# ThermoActuator.net
KiCad netlist of a schematic drawn in EAGLE
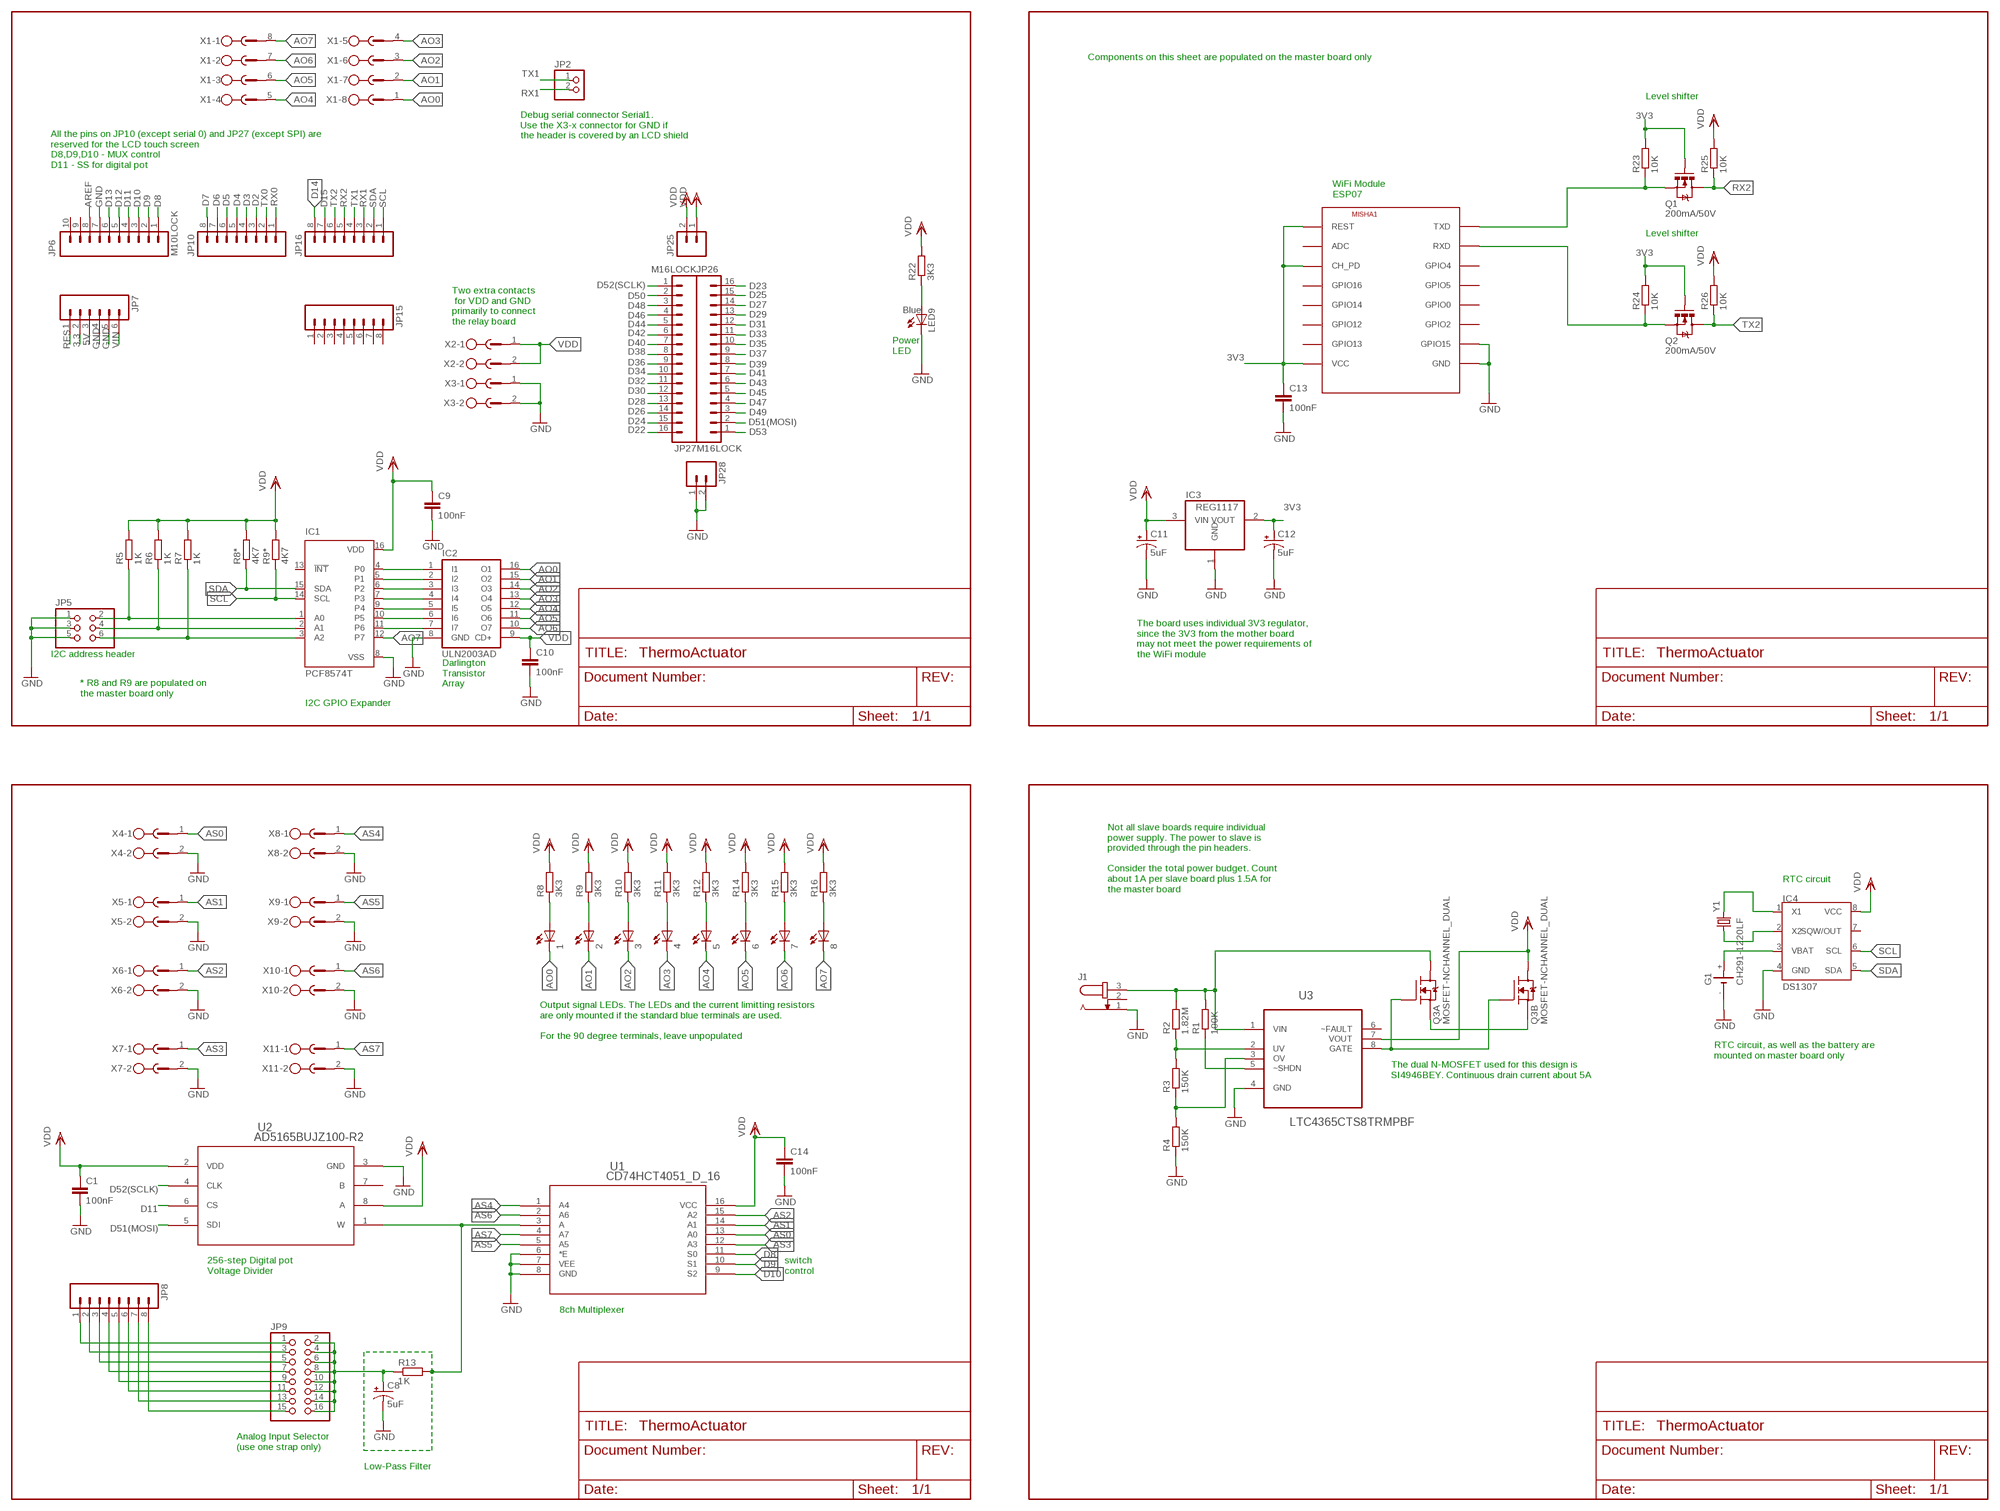
[diagram p0: schematic, sheet 1]

(export (version "E")
  (design (tool "Eeschema 10.0.6"))
  (components
    (comp (ref "1")
      (value "LEDCHIP-LED0805")
      (footprint "eagle-import:CHIP-LED0805")
      (libsource (lib "eagle-import") (part "LEDCHIP-LED0805"))
    )
    (comp (ref "2")
      (value "LEDCHIP-LED0805")
      (footprint "eagle-import:CHIP-LED0805")
      (libsource (lib "eagle-import") (part "LEDCHIP-LED0805"))
    )
    (comp (ref "3")
      (value "LEDCHIP-LED0805")
      (footprint "eagle-import:CHIP-LED0805")
      (libsource (lib "eagle-import") (part "LEDCHIP-LED0805"))
    )
    (comp (ref "4")
      (value "LEDCHIP-LED0805")
      (footprint "eagle-import:CHIP-LED0805")
      (libsource (lib "eagle-import") (part "LEDCHIP-LED0805"))
    )
    (comp (ref "5")
      (value "LEDCHIP-LED0805")
      (footprint "eagle-import:CHIP-LED0805")
      (libsource (lib "eagle-import") (part "LEDCHIP-LED0805"))
    )
    (comp (ref "6")
      (value "LEDCHIP-LED0805")
      (footprint "eagle-import:CHIP-LED0805")
      (libsource (lib "eagle-import") (part "LEDCHIP-LED0805"))
    )
    (comp (ref "7")
      (value "LEDCHIP-LED0805")
      (footprint "eagle-import:CHIP-LED0805")
      (libsource (lib "eagle-import") (part "LEDCHIP-LED0805"))
    )
    (comp (ref "8")
      (value "LEDCHIP-LED0805")
      (footprint "eagle-import:CHIP-LED0805")
      (libsource (lib "eagle-import") (part "LEDCHIP-LED0805"))
    )
    (comp (ref "C1")
      (value "100nF")
      (footprint "eagle-import:C0805")
      (libsource (lib "eagle-import") (part "C-EUC0805"))
    )
    (comp (ref "C8")
      (value "5uF")
      (footprint "eagle-import:EIA3216")
      (libsource (lib "eagle-import") (part "CAP_POL1206"))
    )
    (comp (ref "C9")
      (value "100nF")
      (footprint "eagle-import:C0805")
      (libsource (lib "eagle-import") (part "C-EUC0805"))
    )
    (comp (ref "C10")
      (value "100nF")
      (footprint "eagle-import:C0805")
      (libsource (lib "eagle-import") (part "C-EUC0805"))
    )
    (comp (ref "C11")
      (value "5uF")
      (footprint "eagle-import:EIA3216")
      (libsource (lib "eagle-import") (part "CAP_POL1206"))
    )
    (comp (ref "C12")
      (value "5uF")
      (footprint "eagle-import:EIA3216")
      (libsource (lib "eagle-import") (part "CAP_POL1206"))
    )
    (comp (ref "C13")
      (value "100nF")
      (footprint "eagle-import:C0805")
      (libsource (lib "eagle-import") (part "C-EUC0805"))
    )
    (comp (ref "C14")
      (value "100nF")
      (footprint "eagle-import:C0805")
      (libsource (lib "eagle-import") (part "C-EUC0805"))
    )
    (comp (ref "G1")
      (value "CH291-1220LF")
      (footprint "eagle-import:CH291-1220LF")
      (libsource (lib "eagle-import") (part "CH291-1220LF"))
    )
    (comp (ref "IC1")
      (value "PCF8574T")
      (footprint "eagle-import:SO16W")
      (fields (field (name "MPN") "PCF8574T/3,512"))
      (libsource (lib "eagle-import") (part "PCF8574T"))
    )
    (comp (ref "IC2")
      (value "ULN2003AD")
      (footprint "eagle-import:SO16")
      (libsource (lib "eagle-import") (part "ULN2003AD"))
    )
    (comp (ref "IC3")
      (value "REG1117")
      (footprint "eagle-import:SOT223")
      (libsource (lib "eagle-import") (part "REG1117"))
    )
    (comp (ref "IC4")
      (value "DS1307")
      (footprint "eagle-import:SOIC-8")
      (libsource (lib "eagle-import") (part "DS1307"))
    )
    (comp (ref "J1")
      (value "JACK-PLUG1")
      (footprint "eagle-import:SPC4078")
      (libsource (lib "eagle-import") (part "JACK-PLUG1"))
    )
    (comp (ref "JP2")
      (value "PINHD-1X2")
      (footprint "eagle-import:1X02")
      (libsource (lib "eagle-import") (part "PINHD-1X2"))
    )
    (comp (ref "JP5")
      (value "PINHD-2X3")
      (footprint "eagle-import:2X03")
      (libsource (lib "eagle-import") (part "PINHD-2X3"))
    )
    (comp (ref "JP6")
      (value "M10LOCK")
      (footprint "eagle-import:1X10_LOCK")
      (libsource (lib "eagle-import") (part "M10LOCK"))
    )
    (comp (ref "JP7")
      (value "M06LOCK")
      (footprint "eagle-import:1X06_LOCK")
      (libsource (lib "eagle-import") (part "M06LOCK"))
    )
    (comp (ref "JP8")
      (value "M08LOCK")
      (footprint "eagle-import:1X08_LOCK")
      (libsource (lib "eagle-import") (part "M08LOCK"))
    )
    (comp (ref "JP9")
      (value "PINHD-2X8")
      (footprint "eagle-import:2X08")
      (libsource (lib "eagle-import") (part "PINHD-2X8"))
    )
    (comp (ref "JP10")
      (value "M08LOCK")
      (footprint "eagle-import:1X08_LOCK")
      (libsource (lib "eagle-import") (part "M08LOCK"))
    )
    (comp (ref "JP15")
      (value "M08LOCK")
      (footprint "eagle-import:1X08_LOCK")
      (libsource (lib "eagle-import") (part "M08LOCK"))
    )
    (comp (ref "JP16")
      (value "M08LOCK")
      (footprint "eagle-import:1X08_LOCK")
      (libsource (lib "eagle-import") (part "M08LOCK"))
    )
    (comp (ref "JP25")
      (value "M02LOCK")
      (footprint "eagle-import:1X02_LOCK")
      (libsource (lib "eagle-import") (part "M02LOCK"))
    )
    (comp (ref "JP26")
      (value "M16LOCK")
      (footprint "eagle-import:1X16_LOCK")
      (libsource (lib "eagle-import") (part "M16LOCK"))
    )
    (comp (ref "JP27")
      (value "M16LOCK")
      (footprint "eagle-import:1X16_LOCK")
      (libsource (lib "eagle-import") (part "M16LOCK"))
    )
    (comp (ref "JP28")
      (value "M02LOCK")
      (footprint "eagle-import:1X02_LOCK")
      (libsource (lib "eagle-import") (part "M02LOCK"))
    )
    (comp (ref "LED9")
      (value "Blue")
      (footprint "eagle-import:CHIP-LED0805")
      (libsource (lib "eagle-import") (part "LEDCHIP-LED0805"))
    )
    (comp (ref "MISHA1")
      (value "ESP8266-07")
      (footprint "eagle-import:ESP-07")
      (libsource (lib "eagle-import") (part "ESP8266-07"))
    )
    (comp (ref "Q1")
      (value "200mA/50V")
      (footprint "eagle-import:SOT23-3")
      (libsource (lib "eagle-import") (part "MOSFET-NCHANNELBSS138"))
    )
    (comp (ref "Q2")
      (value "200mA/50V")
      (footprint "eagle-import:SOT23-3")
      (libsource (lib "eagle-import") (part "MOSFET-NCHANNELBSS138"))
    )
    (comp (ref "Q3")
      (value "MOSFET-NCHANNEL_DUAL")
      (footprint "eagle-import:SO08")
      (libsource (lib "eagle-import") (part "MOSFET-NCHANNEL_DUAL"))
    )
    (comp (ref "R1")
      (value "100K")
      (footprint "eagle-import:R0805")
      (libsource (lib "eagle-import") (part "R-EU_R0805"))
    )
    (comp (ref "R2")
      (value "1.82M")
      (footprint "eagle-import:R0805")
      (libsource (lib "eagle-import") (part "R-EU_R0805"))
    )
    (comp (ref "R3")
      (value "150K")
      (footprint "eagle-import:R0805")
      (libsource (lib "eagle-import") (part "R-EU_R0805"))
    )
    (comp (ref "R4")
      (value "150K")
      (footprint "eagle-import:R0805")
      (libsource (lib "eagle-import") (part "R-EU_R0805"))
    )
    (comp (ref "R5")
      (value "1K")
      (footprint "eagle-import:R0805")
      (libsource (lib "eagle-import") (part "R-EU_R0805"))
    )
    (comp (ref "R6")
      (value "1K")
      (footprint "eagle-import:R0805")
      (libsource (lib "eagle-import") (part "R-EU_R0805"))
    )
    (comp (ref "R7")
      (value "1K")
      (footprint "eagle-import:R0805")
      (libsource (lib "eagle-import") (part "R-EU_R0805"))
    )
    (comp (ref "R8")
      (value "3K3")
      (footprint "eagle-import:R0805")
      (libsource (lib "eagle-import") (part "R-EU_R0805"))
    )
    (comp (ref "R8*")
      (value "4K7")
      (footprint "eagle-import:R0805")
      (libsource (lib "eagle-import") (part "R-EU_R0805"))
    )
    (comp (ref "R9")
      (value "3K3")
      (footprint "eagle-import:R0805")
      (libsource (lib "eagle-import") (part "R-EU_R0805"))
    )
    (comp (ref "R9*")
      (value "4K7")
      (footprint "eagle-import:R0805")
      (libsource (lib "eagle-import") (part "R-EU_R0805"))
    )
    (comp (ref "R10")
      (value "3K3")
      (footprint "eagle-import:R0805")
      (libsource (lib "eagle-import") (part "R-EU_R0805"))
    )
    (comp (ref "R11")
      (value "3K3")
      (footprint "eagle-import:R0805")
      (libsource (lib "eagle-import") (part "R-EU_R0805"))
    )
    (comp (ref "R12")
      (value "3K3")
      (footprint "eagle-import:R0805")
      (libsource (lib "eagle-import") (part "R-EU_R0805"))
    )
    (comp (ref "R13")
      (value "1K")
      (footprint "eagle-import:R1206")
      (libsource (lib "eagle-import") (part "R-EU_R1206"))
    )
    (comp (ref "R14")
      (value "3K3")
      (footprint "eagle-import:R0805")
      (libsource (lib "eagle-import") (part "R-EU_R0805"))
    )
    (comp (ref "R15")
      (value "3K3")
      (footprint "eagle-import:R0805")
      (libsource (lib "eagle-import") (part "R-EU_R0805"))
    )
    (comp (ref "R16")
      (value "3K3")
      (footprint "eagle-import:R0805")
      (libsource (lib "eagle-import") (part "R-EU_R0805"))
    )
    (comp (ref "R22")
      (value "3K3")
      (footprint "eagle-import:R0805")
      (libsource (lib "eagle-import") (part "R-EU_R0805"))
    )
    (comp (ref "R23")
      (value "10K")
      (footprint "eagle-import:R0805")
      (libsource (lib "eagle-import") (part "R-EU_R0805"))
    )
    (comp (ref "R24")
      (value "10K")
      (footprint "eagle-import:R0805")
      (libsource (lib "eagle-import") (part "R-EU_R0805"))
    )
    (comp (ref "R25")
      (value "10K")
      (footprint "eagle-import:R0805")
      (libsource (lib "eagle-import") (part "R-EU_R0805"))
    )
    (comp (ref "R26")
      (value "10K")
      (footprint "eagle-import:R0805")
      (libsource (lib "eagle-import") (part "R-EU_R0805"))
    )
    (comp (ref "U1")
      (value "CD74HCT4051_D_16")
      (footprint "eagle-import:D16")
      (fields
        (field (name "GENERIC_PART_NUMBER") "CD74HCT4051")
        (field (name "MANUFACTURER") "Texas Instruments")
      )
      (libsource (lib "eagle-import") (part "CD74HCT4051_D_16"))
    )
    (comp (ref "U2")
      (value "AD5165BUJZ100-R2")
      (footprint "eagle-import:UJ_8")
      (libsource (lib "eagle-import") (part "AD5165BUJZ100-R2"))
    )
    (comp (ref "U3")
      (value "LTC4365CTS8TRMPBF")
      (footprint "eagle-import:SOT65P280X100-8N")
      (fields (field (name "MPN") "LTC4365CTS8#TRMPBF"))
      (libsource (lib "eagle-import") (part "LTC4365CTS8TRMPBF"))
    )
    (comp (ref "X1")
      (value "MSTBV8")
      (footprint "eagle-import:MSTBV8")
      (libsource (lib "eagle-import") (part "MSTBV8"))
    )
    (comp (ref "X2")
      (value "MSTBV2")
      (footprint "eagle-import:MSTBV2")
      (libsource (lib "eagle-import") (part "MSTBV2"))
    )
    (comp (ref "X3")
      (value "MSTBV2")
      (footprint "eagle-import:MSTBV2")
      (libsource (lib "eagle-import") (part "MSTBV2"))
    )
    (comp (ref "X4")
      (value "MSTBV2")
      (footprint "eagle-import:MSTBV2")
      (libsource (lib "eagle-import") (part "MSTBV2"))
    )
    (comp (ref "X5")
      (value "MSTBV2")
      (footprint "eagle-import:MSTBV2")
      (libsource (lib "eagle-import") (part "MSTBV2"))
    )
    (comp (ref "X6")
      (value "MSTBV2")
      (footprint "eagle-import:MSTBV2")
      (libsource (lib "eagle-import") (part "MSTBV2"))
    )
    (comp (ref "X7")
      (value "MSTBV2")
      (footprint "eagle-import:MSTBV2")
      (libsource (lib "eagle-import") (part "MSTBV2"))
    )
    (comp (ref "X8")
      (value "MSTBV2")
      (footprint "eagle-import:MSTBV2")
      (libsource (lib "eagle-import") (part "MSTBV2"))
    )
    (comp (ref "X9")
      (value "MSTBV2")
      (footprint "eagle-import:MSTBV2")
      (libsource (lib "eagle-import") (part "MSTBV2"))
    )
    (comp (ref "X10")
      (value "MSTBV2")
      (footprint "eagle-import:MSTBV2")
      (libsource (lib "eagle-import") (part "MSTBV2"))
    )
    (comp (ref "X11")
      (value "MSTBV2")
      (footprint "eagle-import:MSTBV2")
      (libsource (lib "eagle-import") (part "MSTBV2"))
    )
    (comp (ref "Y1")
      (value "CRYSTAL3.2X1.5MM")
      (footprint "eagle-import:CRYSTAL-SMD-3.2X1.5MM")
      (libsource (lib "eagle-import") (part "CRYSTAL3.2X1.5MM"))
    )
  )
  (nets
    (net (code "1") (name "/3.3") (class "Default")
      (node (ref "JP7") (pin "2") (pinfunction "2_2") (pintype "passive"))
    )
    (net (code "2") (name "/3V3") (class "Default")
      (node (ref "C12") (pin "A") (pinfunction "+_A") (pintype "passive"))
      (node (ref "C13") (pin "1") (pinfunction "1_1") (pintype "passive"))
      (node (ref "IC3") (pin "2") (pinfunction "VOUT_2") (pintype "output"))
      (node (ref "MISHA1") (pin "CH_PD") (pinfunction "CH_PD_CH_PD") (pintype "input"))
      (node (ref "MISHA1") (pin "REST") (pinfunction "REST_REST") (pintype "bidirectional"))
      (node (ref "MISHA1") (pin "VCC") (pinfunction "VCC_VCC") (pintype "power_in"))
      (node (ref "Q1") (pin "1") (pinfunction "G_1") (pintype "passive"))
      (node (ref "Q2") (pin "1") (pinfunction "G_1") (pintype "passive"))
      (node (ref "R23") (pin "2") (pinfunction "2_2") (pintype "passive"))
      (node (ref "R24") (pin "2") (pinfunction "2_2") (pintype "passive"))
    )
    (net (code "3") (name "/5V") (class "Default")
      (node (ref "JP7") (pin "3") (pinfunction "3_3") (pintype "passive"))
    )
    (net (code "4") (name "/AREF") (class "Default")
      (node (ref "JP6") (pin "8") (pinfunction "8_8") (pintype "passive"))
    )
    (net (code "5") (name "/D2") (class "Default")
      (node (ref "JP10") (pin "3") (pinfunction "3_3") (pintype "passive"))
    )
    (net (code "6") (name "/D3") (class "Default")
      (node (ref "JP10") (pin "4") (pinfunction "4_4") (pintype "passive"))
    )
    (net (code "7") (name "/D4") (class "Default")
      (node (ref "JP10") (pin "5") (pinfunction "5_5") (pintype "passive"))
    )
    (net (code "8") (name "/D5") (class "Default")
      (node (ref "JP10") (pin "6") (pinfunction "6_6") (pintype "passive"))
    )
    (net (code "9") (name "/D6") (class "Default")
      (node (ref "JP10") (pin "7") (pinfunction "7_7") (pintype "passive"))
    )
    (net (code "10") (name "/D7") (class "Default")
      (node (ref "JP10") (pin "8") (pinfunction "8_8") (pintype "passive"))
    )
    (net (code "11") (name "/D11") (class "Default")
      (node (ref "JP6") (pin "4") (pinfunction "4_4") (pintype "passive"))
      (node (ref "U2") (pin "6") (pinfunction "CS_6") (pintype "passive"))
    )
    (net (code "12") (name "/D12") (class "Default")
      (node (ref "JP6") (pin "5") (pinfunction "5_5") (pintype "passive"))
    )
    (net (code "13") (name "/D13") (class "Default")
      (node (ref "JP6") (pin "6") (pinfunction "6_6") (pintype "passive"))
    )
    (net (code "14") (name "/D15") (class "Default")
      (node (ref "JP16") (pin "7") (pinfunction "7_7") (pintype "passive"))
    )
    (net (code "15") (name "/D22") (class "Default")
      (node (ref "JP27") (pin "16") (pinfunction "16_16") (pintype "passive"))
    )
    (net (code "16") (name "/D23") (class "Default")
      (node (ref "JP26") (pin "16") (pinfunction "16_16") (pintype "passive"))
    )
    (net (code "17") (name "/D24") (class "Default")
      (node (ref "JP27") (pin "15") (pinfunction "15_15") (pintype "passive"))
    )
    (net (code "18") (name "/D25") (class "Default")
      (node (ref "JP26") (pin "15") (pinfunction "15_15") (pintype "passive"))
    )
    (net (code "19") (name "/D26") (class "Default")
      (node (ref "JP27") (pin "14") (pinfunction "14_14") (pintype "passive"))
    )
    (net (code "20") (name "/D27") (class "Default")
      (node (ref "JP26") (pin "14") (pinfunction "14_14") (pintype "passive"))
    )
    (net (code "21") (name "/D28") (class "Default")
      (node (ref "JP27") (pin "13") (pinfunction "13_13") (pintype "passive"))
    )
    (net (code "22") (name "/D29") (class "Default")
      (node (ref "JP26") (pin "13") (pinfunction "13_13") (pintype "passive"))
    )
    (net (code "23") (name "/D30") (class "Default")
      (node (ref "JP27") (pin "12") (pinfunction "12_12") (pintype "passive"))
    )
    (net (code "24") (name "/D31") (class "Default")
      (node (ref "JP26") (pin "12") (pinfunction "12_12") (pintype "passive"))
    )
    (net (code "25") (name "/D32") (class "Default")
      (node (ref "JP27") (pin "11") (pinfunction "11_11") (pintype "passive"))
    )
    (net (code "26") (name "/D33") (class "Default")
      (node (ref "JP26") (pin "11") (pinfunction "11_11") (pintype "passive"))
    )
    (net (code "27") (name "/D34") (class "Default")
      (node (ref "JP27") (pin "10") (pinfunction "10_10") (pintype "passive"))
    )
    (net (code "28") (name "/D35") (class "Default")
      (node (ref "JP26") (pin "10") (pinfunction "10_10") (pintype "passive"))
    )
    (net (code "29") (name "/D36") (class "Default")
      (node (ref "JP27") (pin "9") (pinfunction "9_9") (pintype "passive"))
    )
    (net (code "30") (name "/D37") (class "Default")
      (node (ref "JP26") (pin "9") (pinfunction "9_9") (pintype "passive"))
    )
    (net (code "31") (name "/D38") (class "Default")
      (node (ref "JP27") (pin "8") (pinfunction "8_8") (pintype "passive"))
    )
    (net (code "32") (name "/D39") (class "Default")
      (node (ref "JP26") (pin "8") (pinfunction "8_8") (pintype "passive"))
    )
    (net (code "33") (name "/D40") (class "Default")
      (node (ref "JP27") (pin "7") (pinfunction "7_7") (pintype "passive"))
    )
    (net (code "34") (name "/D41") (class "Default")
      (node (ref "JP26") (pin "7") (pinfunction "7_7") (pintype "passive"))
    )
    (net (code "35") (name "/D42") (class "Default")
      (node (ref "JP27") (pin "6") (pinfunction "6_6") (pintype "passive"))
    )
    (net (code "36") (name "/D43") (class "Default")
      (node (ref "JP26") (pin "6") (pinfunction "6_6") (pintype "passive"))
    )
    (net (code "37") (name "/D44") (class "Default")
      (node (ref "JP27") (pin "5") (pinfunction "5_5") (pintype "passive"))
    )
    (net (code "38") (name "/D45") (class "Default")
      (node (ref "JP26") (pin "5") (pinfunction "5_5") (pintype "passive"))
    )
    (net (code "39") (name "/D46") (class "Default")
      (node (ref "JP27") (pin "4") (pinfunction "4_4") (pintype "passive"))
    )
    (net (code "40") (name "/D47") (class "Default")
      (node (ref "JP26") (pin "4") (pinfunction "4_4") (pintype "passive"))
    )
    (net (code "41") (name "/D48") (class "Default")
      (node (ref "JP27") (pin "3") (pinfunction "3_3") (pintype "passive"))
    )
    (net (code "42") (name "/D49") (class "Default")
      (node (ref "JP26") (pin "3") (pinfunction "3_3") (pintype "passive"))
    )
    (net (code "43") (name "/D50") (class "Default")
      (node (ref "JP27") (pin "2") (pinfunction "2_2") (pintype "passive"))
    )
    (net (code "44") (name "/D51(MOSI)") (class "Default")
      (node (ref "JP26") (pin "2") (pinfunction "2_2") (pintype "passive"))
      (node (ref "U2") (pin "5") (pinfunction "SDI_5") (pintype "passive"))
    )
    (net (code "45") (name "/D52(SCLK)") (class "Default")
      (node (ref "JP27") (pin "1") (pinfunction "1_1") (pintype "passive"))
      (node (ref "U2") (pin "4") (pinfunction "CLK_4") (pintype "passive"))
    )
    (net (code "46") (name "/D53") (class "Default")
      (node (ref "JP26") (pin "1") (pinfunction "1_1") (pintype "passive"))
    )
    (net (code "47") (name "/RES") (class "Default")
      (node (ref "JP7") (pin "1") (pinfunction "1_1") (pintype "passive"))
    )
    (net (code "48") (name "/RX0") (class "Default")
      (node (ref "JP10") (pin "1") (pinfunction "1_1") (pintype "passive"))
    )
    (net (code "49") (name "/RX1") (class "Default")
      (node (ref "JP16") (pin "3") (pinfunction "3_3") (pintype "passive"))
      (node (ref "JP2") (pin "2") (pinfunction "2_2") (pintype "passive"))
    )
    (net (code "50") (name "/TX0") (class "Default")
      (node (ref "JP10") (pin "2") (pinfunction "2_2") (pintype "passive"))
    )
    (net (code "51") (name "/TX1") (class "Default")
      (node (ref "JP16") (pin "4") (pinfunction "4_4") (pintype "passive"))
      (node (ref "JP2") (pin "1") (pinfunction "1_1") (pintype "passive"))
    )
    (net (code "52") (name "/VIN") (class "Default")
      (node (ref "JP7") (pin "6") (pinfunction "6_6") (pintype "passive"))
    )
    (net (code "53") (name "AO0") (class "Default")
      (node (ref "1") (pin "C") (pinfunction "C_C") (pintype "passive"))
      (node (ref "IC2") (pin "16") (pinfunction "O1_16") (pintype "open_collector"))
      (node (ref "X1") (pin "1") (pinfunction "SK_1") (pintype "passive"))
    )
    (net (code "54") (name "AO1") (class "Default")
      (node (ref "2") (pin "C") (pinfunction "C_C") (pintype "passive"))
      (node (ref "IC2") (pin "15") (pinfunction "O2_15") (pintype "open_collector"))
      (node (ref "X1") (pin "2") (pinfunction "SK_2") (pintype "passive"))
    )
    (net (code "55") (name "AO2") (class "Default")
      (node (ref "3") (pin "C") (pinfunction "C_C") (pintype "passive"))
      (node (ref "IC2") (pin "14") (pinfunction "O3_14") (pintype "open_collector"))
      (node (ref "X1") (pin "3") (pinfunction "SK_3") (pintype "passive"))
    )
    (net (code "56") (name "AO3") (class "Default")
      (node (ref "4") (pin "C") (pinfunction "C_C") (pintype "passive"))
      (node (ref "IC2") (pin "13") (pinfunction "O4_13") (pintype "open_collector"))
      (node (ref "X1") (pin "4") (pinfunction "SK_4") (pintype "passive"))
    )
    (net (code "57") (name "AO4") (class "Default")
      (node (ref "5") (pin "C") (pinfunction "C_C") (pintype "passive"))
      (node (ref "IC2") (pin "12") (pinfunction "O5_12") (pintype "open_collector"))
      (node (ref "X1") (pin "5") (pinfunction "SK_5") (pintype "passive"))
    )
    (net (code "58") (name "AO5") (class "Default")
      (node (ref "6") (pin "C") (pinfunction "C_C") (pintype "passive"))
      (node (ref "IC2") (pin "11") (pinfunction "O6_11") (pintype "open_collector"))
      (node (ref "X1") (pin "6") (pinfunction "SK_6") (pintype "passive"))
    )
    (net (code "59") (name "AO6") (class "Default")
      (node (ref "7") (pin "C") (pinfunction "C_C") (pintype "passive"))
      (node (ref "IC2") (pin "10") (pinfunction "O7_10") (pintype "open_collector"))
      (node (ref "X1") (pin "7") (pinfunction "SK_7") (pintype "passive"))
    )
    (net (code "60") (name "AO7") (class "Default")
      (node (ref "8") (pin "C") (pinfunction "C_C") (pintype "passive"))
      (node (ref "IC1") (pin "12") (pinfunction "P7_12") (pintype "bidirectional"))
      (node (ref "X1") (pin "8") (pinfunction "SK_8") (pintype "passive"))
    )
    (net (code "61") (name "AS0") (class "Default")
      (node (ref "U1") (pin "13") (pinfunction "A0_13") (pintype "bidirectional"))
      (node (ref "X4") (pin "1") (pinfunction "SK_1") (pintype "passive"))
    )
    (net (code "62") (name "AS1") (class "Default")
      (node (ref "U1") (pin "14") (pinfunction "A1_14") (pintype "bidirectional"))
      (node (ref "X5") (pin "1") (pinfunction "SK_1") (pintype "passive"))
    )
    (net (code "63") (name "AS2") (class "Default")
      (node (ref "U1") (pin "15") (pinfunction "A2_15") (pintype "bidirectional"))
      (node (ref "X6") (pin "1") (pinfunction "SK_1") (pintype "passive"))
    )
    (net (code "64") (name "AS3") (class "Default")
      (node (ref "U1") (pin "12") (pinfunction "A3_12") (pintype "bidirectional"))
      (node (ref "X7") (pin "1") (pinfunction "SK_1") (pintype "passive"))
    )
    (net (code "65") (name "AS4") (class "Default")
      (node (ref "U1") (pin "1") (pinfunction "A4_1") (pintype "bidirectional"))
      (node (ref "X8") (pin "1") (pinfunction "SK_1") (pintype "passive"))
    )
    (net (code "66") (name "AS5") (class "Default")
      (node (ref "U1") (pin "5") (pinfunction "A5_5") (pintype "bidirectional"))
      (node (ref "X9") (pin "1") (pinfunction "SK_1") (pintype "passive"))
    )
    (net (code "67") (name "AS6") (class "Default")
      (node (ref "U1") (pin "2") (pinfunction "A6_2") (pintype "bidirectional"))
      (node (ref "X10") (pin "1") (pinfunction "SK_1") (pintype "passive"))
    )
    (net (code "68") (name "AS7") (class "Default")
      (node (ref "U1") (pin "4") (pinfunction "A7_4") (pintype "bidirectional"))
      (node (ref "X11") (pin "1") (pinfunction "SK_1") (pintype "passive"))
    )
    (net (code "69") (name "D8") (class "Default")
      (node (ref "JP6") (pin "1") (pinfunction "1_1") (pintype "passive"))
      (node (ref "U1") (pin "11") (pinfunction "S0_11") (pintype "output"))
    )
    (net (code "70") (name "D9") (class "Default")
      (node (ref "JP6") (pin "2") (pinfunction "2_2") (pintype "passive"))
      (node (ref "U1") (pin "10") (pinfunction "S1_10") (pintype "output"))
    )
    (net (code "71") (name "D10") (class "Default")
      (node (ref "JP6") (pin "3") (pinfunction "3_3") (pintype "passive"))
      (node (ref "U1") (pin "9") (pinfunction "S2_9") (pintype "output"))
    )
    (net (code "72") (name "D14") (class "Default")
      (node (ref "JP16") (pin "8") (pinfunction "8_8") (pintype "passive"))
    )
    (net (code "73") (name "GND") (class "Default")
      (node (ref "C1") (pin "2") (pinfunction "2_2") (pintype "passive"))
      (node (ref "C10") (pin "2") (pinfunction "2_2") (pintype "passive"))
      (node (ref "C11") (pin "C") (pinfunction "-_C") (pintype "passive"))
      (node (ref "C12") (pin "C") (pinfunction "-_C") (pintype "passive"))
      (node (ref "C13") (pin "2") (pinfunction "2_2") (pintype "passive"))
      (node (ref "C14") (pin "2") (pinfunction "2_2") (pintype "passive"))
      (node (ref "C8") (pin "C") (pinfunction "-_C") (pintype "passive"))
      (node (ref "C9") (pin "2") (pinfunction "2_2") (pintype "passive"))
      (node (ref "G1") (pin "-") (pinfunction "-_-") (pintype "passive"))
      (node (ref "IC1") (pin "8") (pinfunction "VSS_8") (pintype "power_in"))
      (node (ref "IC2") (pin "8") (pinfunction "GND_8") (pintype "power_in"))
      (node (ref "IC3") (pin "1") (pinfunction "GND_1") (pintype "power_in"))
      (node (ref "IC4") (pin "4") (pinfunction "GND_4") (pintype "power_in"))
      (node (ref "J1") (pin "1") (pinfunction "1_1") (pintype "passive"))
      (node (ref "JP28") (pin "1") (pinfunction "1_1") (pintype "passive"))
      (node (ref "JP28") (pin "2") (pinfunction "2_2") (pintype "passive"))
      (node (ref "JP5") (pin "1") (pinfunction "1_1") (pintype "passive"))
      (node (ref "JP5") (pin "3") (pinfunction "3_3") (pintype "passive"))
      (node (ref "JP5") (pin "5") (pinfunction "5_5") (pintype "passive"))
      (node (ref "JP6") (pin "7") (pinfunction "7_7") (pintype "passive"))
      (node (ref "JP7") (pin "4") (pinfunction "4_4") (pintype "passive"))
      (node (ref "JP7") (pin "5") (pinfunction "5_5") (pintype "passive"))
      (node (ref "LED9") (pin "C") (pinfunction "C_C") (pintype "passive"))
      (node (ref "MISHA1") (pin "GND") (pinfunction "GND_GND") (pintype "power_in"))
      (node (ref "MISHA1") (pin "GPIO15") (pinfunction "GPIO15_GPIO15") (pintype "input"))
      (node (ref "R4") (pin "1") (pinfunction "1_1") (pintype "passive"))
      (node (ref "U1") (pin "6") (pinfunction "*E_6") (pintype "input"))
      (node (ref "U1") (pin "7") (pinfunction "VEE_7") (pintype "power_in"))
      (node (ref "U1") (pin "8") (pinfunction "GND_8") (pintype "power_in"))
      (node (ref "U2") (pin "3") (pinfunction "GND_3") (pintype "passive"))
      (node (ref "U3") (pin "4") (pinfunction "GND_4") (pintype "passive"))
      (node (ref "X10") (pin "2") (pinfunction "SK_2") (pintype "passive"))
      (node (ref "X11") (pin "2") (pinfunction "SK_2") (pintype "passive"))
      (node (ref "X3") (pin "1") (pinfunction "SK_1") (pintype "passive"))
      (node (ref "X3") (pin "2") (pinfunction "SK_2") (pintype "passive"))
      (node (ref "X4") (pin "2") (pinfunction "SK_2") (pintype "passive"))
      (node (ref "X5") (pin "2") (pinfunction "SK_2") (pintype "passive"))
      (node (ref "X6") (pin "2") (pinfunction "SK_2") (pintype "passive"))
      (node (ref "X7") (pin "2") (pinfunction "SK_2") (pintype "passive"))
      (node (ref "X8") (pin "2") (pinfunction "SK_2") (pintype "passive"))
      (node (ref "X9") (pin "2") (pinfunction "SK_2") (pintype "passive"))
    )
    (net (code "74") (name "Net-(1-PadA)") (class "Default")
      (node (ref "1") (pin "A") (pinfunction "A_A") (pintype "passive"))
      (node (ref "R8") (pin "1") (pinfunction "1_1") (pintype "passive"))
    )
    (net (code "75") (name "Net-(2-PadA)") (class "Default")
      (node (ref "2") (pin "A") (pinfunction "A_A") (pintype "passive"))
      (node (ref "R9") (pin "1") (pinfunction "1_1") (pintype "passive"))
    )
    (net (code "76") (name "Net-(3-PadA)") (class "Default")
      (node (ref "3") (pin "A") (pinfunction "A_A") (pintype "passive"))
      (node (ref "R10") (pin "1") (pinfunction "1_1") (pintype "passive"))
    )
    (net (code "77") (name "Net-(4-PadA)") (class "Default")
      (node (ref "4") (pin "A") (pinfunction "A_A") (pintype "passive"))
      (node (ref "R11") (pin "1") (pinfunction "1_1") (pintype "passive"))
    )
    (net (code "78") (name "Net-(5-PadA)") (class "Default")
      (node (ref "5") (pin "A") (pinfunction "A_A") (pintype "passive"))
      (node (ref "R12") (pin "1") (pinfunction "1_1") (pintype "passive"))
    )
    (net (code "79") (name "Net-(6-PadA)") (class "Default")
      (node (ref "6") (pin "A") (pinfunction "A_A") (pintype "passive"))
      (node (ref "R14") (pin "1") (pinfunction "1_1") (pintype "passive"))
    )
    (net (code "80") (name "Net-(7-PadA)") (class "Default")
      (node (ref "7") (pin "A") (pinfunction "A_A") (pintype "passive"))
      (node (ref "R15") (pin "1") (pinfunction "1_1") (pintype "passive"))
    )
    (net (code "81") (name "Net-(8-PadA)") (class "Default")
      (node (ref "8") (pin "A") (pinfunction "A_A") (pintype "passive"))
      (node (ref "R16") (pin "1") (pinfunction "1_1") (pintype "passive"))
    )
    (net (code "82") (name "Net-(C8-+)") (class "Default")
      (node (ref "C8") (pin "A") (pinfunction "+_A") (pintype "passive"))
      (node (ref "JP9") (pin "10") (pinfunction "10_10") (pintype "passive"))
      (node (ref "JP9") (pin "12") (pinfunction "12_12") (pintype "passive"))
      (node (ref "JP9") (pin "14") (pinfunction "14_14") (pintype "passive"))
      (node (ref "JP9") (pin "16") (pinfunction "16_16") (pintype "passive"))
      (node (ref "JP9") (pin "2") (pinfunction "2_2") (pintype "passive"))
      (node (ref "JP9") (pin "4") (pinfunction "4_4") (pintype "passive"))
      (node (ref "JP9") (pin "6") (pinfunction "6_6") (pintype "passive"))
      (node (ref "JP9") (pin "8") (pinfunction "8_8") (pintype "passive"))
      (node (ref "R13") (pin "1") (pinfunction "1_1") (pintype "passive"))
    )
    (net (code "83") (name "Net-(IC1-A0)") (class "Default")
      (node (ref "IC1") (pin "1") (pinfunction "A0_1") (pintype "input"))
      (node (ref "JP5") (pin "2") (pinfunction "2_2") (pintype "passive"))
      (node (ref "R5") (pin "1") (pinfunction "1_1") (pintype "passive"))
    )
    (net (code "84") (name "Net-(IC1-A1)") (class "Default")
      (node (ref "IC1") (pin "2") (pinfunction "A1_2") (pintype "input"))
      (node (ref "JP5") (pin "4") (pinfunction "4_4") (pintype "passive"))
      (node (ref "R6") (pin "1") (pinfunction "1_1") (pintype "passive"))
    )
    (net (code "85") (name "Net-(IC1-A2)") (class "Default")
      (node (ref "IC1") (pin "3") (pinfunction "A2_3") (pintype "input"))
      (node (ref "JP5") (pin "6") (pinfunction "6_6") (pintype "passive"))
      (node (ref "R7") (pin "1") (pinfunction "1_1") (pintype "passive"))
    )
    (net (code "86") (name "Net-(IC1-P0)") (class "Default")
      (node (ref "IC1") (pin "4") (pinfunction "P0_4") (pintype "bidirectional"))
      (node (ref "IC2") (pin "1") (pinfunction "I1_1") (pintype "input"))
    )
    (net (code "87") (name "Net-(IC1-P1)") (class "Default")
      (node (ref "IC1") (pin "5") (pinfunction "P1_5") (pintype "bidirectional"))
      (node (ref "IC2") (pin "2") (pinfunction "I2_2") (pintype "input"))
    )
    (net (code "88") (name "Net-(IC1-P2)") (class "Default")
      (node (ref "IC1") (pin "6") (pinfunction "P2_6") (pintype "bidirectional"))
      (node (ref "IC2") (pin "3") (pinfunction "I3_3") (pintype "input"))
    )
    (net (code "89") (name "Net-(IC1-P3)") (class "Default")
      (node (ref "IC1") (pin "7") (pinfunction "P3_7") (pintype "bidirectional"))
      (node (ref "IC2") (pin "4") (pinfunction "I4_4") (pintype "input"))
    )
    (net (code "90") (name "Net-(IC1-P4)") (class "Default")
      (node (ref "IC1") (pin "9") (pinfunction "P4_9") (pintype "bidirectional"))
      (node (ref "IC2") (pin "5") (pinfunction "I5_5") (pintype "input"))
    )
    (net (code "91") (name "Net-(IC1-P5)") (class "Default")
      (node (ref "IC1") (pin "10") (pinfunction "P5_10") (pintype "bidirectional"))
      (node (ref "IC2") (pin "6") (pinfunction "I6_6") (pintype "input"))
    )
    (net (code "92") (name "Net-(IC1-P6)") (class "Default")
      (node (ref "IC1") (pin "11") (pinfunction "P6_11") (pintype "bidirectional"))
      (node (ref "IC2") (pin "7") (pinfunction "I7_7") (pintype "input"))
    )
    (net (code "93") (name "Net-(IC4-VBAT)") (class "Default")
      (node (ref "G1") (pin "+") (pinfunction "+_+") (pintype "passive"))
      (node (ref "IC4") (pin "3") (pinfunction "VBAT_3") (pintype "power_in"))
    )
    (net (code "94") (name "Net-(IC4-X1)") (class "Default")
      (node (ref "IC4") (pin "1") (pinfunction "X1_1") (pintype "input"))
      (node (ref "Y1") (pin "P$2") (pinfunction "2_P$2") (pintype "passive"))
    )
    (net (code "95") (name "Net-(IC4-X2)") (class "Default")
      (node (ref "IC4") (pin "2") (pinfunction "X2_2") (pintype "output"))
      (node (ref "Y1") (pin "P$1") (pinfunction "1_P$1") (pintype "passive"))
    )
    (net (code "96") (name "Net-(JP8-Pad1)") (class "Default")
      (node (ref "JP8") (pin "1") (pinfunction "1_1") (pintype "passive"))
      (node (ref "JP9") (pin "1") (pinfunction "1_1") (pintype "passive"))
    )
    (net (code "97") (name "Net-(JP8-Pad2)") (class "Default")
      (node (ref "JP8") (pin "2") (pinfunction "2_2") (pintype "passive"))
      (node (ref "JP9") (pin "3") (pinfunction "3_3") (pintype "passive"))
    )
    (net (code "98") (name "Net-(JP8-Pad3)") (class "Default")
      (node (ref "JP8") (pin "3") (pinfunction "3_3") (pintype "passive"))
      (node (ref "JP9") (pin "5") (pinfunction "5_5") (pintype "passive"))
    )
    (net (code "99") (name "Net-(JP8-Pad4)") (class "Default")
      (node (ref "JP8") (pin "4") (pinfunction "4_4") (pintype "passive"))
      (node (ref "JP9") (pin "7") (pinfunction "7_7") (pintype "passive"))
    )
    (net (code "100") (name "Net-(JP8-Pad5)") (class "Default")
      (node (ref "JP8") (pin "5") (pinfunction "5_5") (pintype "passive"))
      (node (ref "JP9") (pin "9") (pinfunction "9_9") (pintype "passive"))
    )
    (net (code "101") (name "Net-(JP8-Pad6)") (class "Default")
      (node (ref "JP8") (pin "6") (pinfunction "6_6") (pintype "passive"))
      (node (ref "JP9") (pin "11") (pinfunction "11_11") (pintype "passive"))
    )
    (net (code "102") (name "Net-(JP8-Pad7)") (class "Default")
      (node (ref "JP8") (pin "7") (pinfunction "7_7") (pintype "passive"))
      (node (ref "JP9") (pin "13") (pinfunction "13_13") (pintype "passive"))
    )
    (net (code "103") (name "Net-(JP8-Pad8)") (class "Default")
      (node (ref "JP8") (pin "8") (pinfunction "8_8") (pintype "passive"))
      (node (ref "JP9") (pin "15") (pinfunction "15_15") (pintype "passive"))
    )
    (net (code "104") (name "Net-(LED9-PadA)") (class "Default")
      (node (ref "LED9") (pin "A") (pinfunction "A_A") (pintype "passive"))
      (node (ref "R22") (pin "1") (pinfunction "1_1") (pintype "passive"))
    )
    (net (code "105") (name "Net-(Q1-S)") (class "Default")
      (node (ref "MISHA1") (pin "TXD") (pinfunction "TXD_TXD") (pintype "output"))
      (node (ref "Q1") (pin "2") (pinfunction "S_2") (pintype "passive"))
      (node (ref "R23") (pin "1") (pinfunction "1_1") (pintype "passive"))
    )
    (net (code "106") (name "Net-(Q2-S)") (class "Default")
      (node (ref "MISHA1") (pin "RXD") (pinfunction "RXD_RXD") (pintype "input"))
      (node (ref "Q2") (pin "2") (pinfunction "S_2") (pintype "passive"))
      (node (ref "R24") (pin "1") (pinfunction "1_1") (pintype "passive"))
    )
    (net (code "107") (name "Net-(Q3A-D1)") (class "Default")
      (node (ref "J1") (pin "3") (pinfunction "3_3") (pintype "passive"))
      (node (ref "Q3") (pin "6") (pinfunction "D1_6") (pintype "passive"))
      (node (ref "R1") (pin "2") (pinfunction "2_2") (pintype "passive"))
      (node (ref "R2") (pin "2") (pinfunction "2_2") (pintype "passive"))
      (node (ref "U3") (pin "1") (pinfunction "VIN_1") (pintype "power_in"))
    )
    (net (code "108") (name "Net-(Q3A-G)") (class "Default")
      (node (ref "Q3") (pin "2") (pinfunction "G_2") (pintype "passive"))
      (node (ref "Q3") (pin "4") (pinfunction "G_4") (pintype "passive"))
      (node (ref "U3") (pin "8") (pinfunction "GATE_8") (pintype "output"))
    )
    (net (code "109") (name "Net-(Q3A-S)") (class "Default")
      (node (ref "Q3") (pin "1") (pinfunction "S_1") (pintype "passive"))
      (node (ref "Q3") (pin "3") (pinfunction "S_3") (pintype "passive"))
    )
    (net (code "110") (name "Net-(U1-A)") (class "Default")
      (node (ref "R13") (pin "2") (pinfunction "2_2") (pintype "passive"))
      (node (ref "U1") (pin "3") (pinfunction "A_3") (pintype "bidirectional"))
      (node (ref "U2") (pin "1") (pinfunction "W_1") (pintype "passive"))
    )
    (net (code "111") (name "Net-(U3-OV)") (class "Default")
      (node (ref "R3") (pin "1") (pinfunction "1_1") (pintype "passive"))
      (node (ref "R4") (pin "2") (pinfunction "2_2") (pintype "passive"))
      (node (ref "U3") (pin "3") (pinfunction "OV_3") (pintype "input"))
    )
    (net (code "112") (name "Net-(U3-UV)") (class "Default")
      (node (ref "R2") (pin "1") (pinfunction "1_1") (pintype "passive"))
      (node (ref "R3") (pin "2") (pinfunction "2_2") (pintype "passive"))
      (node (ref "U3") (pin "2") (pinfunction "UV_2") (pintype "input"))
    )
    (net (code "113") (name "Net-(U3-~{SHDN})") (class "Default")
      (node (ref "R1") (pin "1") (pinfunction "1_1") (pintype "passive"))
      (node (ref "U3") (pin "5") (pinfunction "~{SHDN}_5") (pintype "input"))
    )
    (net (code "114") (name "RX2") (class "Default")
      (node (ref "JP16") (pin "5") (pinfunction "5_5") (pintype "passive"))
      (node (ref "Q1") (pin "3") (pinfunction "D_3") (pintype "passive"))
      (node (ref "R25") (pin "1") (pinfunction "1_1") (pintype "passive"))
    )
    (net (code "115") (name "SCL") (class "Default")
      (node (ref "IC1") (pin "14") (pinfunction "SCL_14") (pintype "input"))
      (node (ref "IC4") (pin "6") (pinfunction "SCL_6") (pintype "input"))
      (node (ref "JP16") (pin "1") (pinfunction "1_1") (pintype "passive"))
      (node (ref "R9*") (pin "1") (pinfunction "1_1") (pintype "passive"))
    )
    (net (code "116") (name "SDA") (class "Default")
      (node (ref "IC1") (pin "15") (pinfunction "SDA_15") (pintype "bidirectional"))
      (node (ref "IC4") (pin "5") (pinfunction "SDA_5") (pintype "bidirectional"))
      (node (ref "JP16") (pin "2") (pinfunction "2_2") (pintype "passive"))
      (node (ref "R8*") (pin "1") (pinfunction "1_1") (pintype "passive"))
    )
    (net (code "117") (name "TX2") (class "Default")
      (node (ref "JP16") (pin "6") (pinfunction "6_6") (pintype "passive"))
      (node (ref "Q2") (pin "3") (pinfunction "D_3") (pintype "passive"))
      (node (ref "R26") (pin "1") (pinfunction "1_1") (pintype "passive"))
    )
    (net (code "118") (name "VDD") (class "Default")
      (node (ref "C1") (pin "1") (pinfunction "1_1") (pintype "passive"))
      (node (ref "C10") (pin "1") (pinfunction "1_1") (pintype "passive"))
      (node (ref "C11") (pin "A") (pinfunction "+_A") (pintype "passive"))
      (node (ref "C14") (pin "1") (pinfunction "1_1") (pintype "passive"))
      (node (ref "C9") (pin "1") (pinfunction "1_1") (pintype "passive"))
      (node (ref "IC1") (pin "16") (pinfunction "VDD_16") (pintype "power_in"))
      (node (ref "IC2") (pin "9") (pinfunction "CD+_9") (pintype "passive"))
      (node (ref "IC3") (pin "3") (pinfunction "VIN_3") (pintype "input"))
      (node (ref "IC4") (pin "8") (pinfunction "VCC_8") (pintype "power_in"))
      (node (ref "JP25") (pin "1") (pinfunction "1_1") (pintype "passive"))
      (node (ref "JP25") (pin "2") (pinfunction "2_2") (pintype "passive"))
      (node (ref "Q3") (pin "8") (pinfunction "D1_8") (pintype "passive"))
      (node (ref "R10") (pin "2") (pinfunction "2_2") (pintype "passive"))
      (node (ref "R11") (pin "2") (pinfunction "2_2") (pintype "passive"))
      (node (ref "R12") (pin "2") (pinfunction "2_2") (pintype "passive"))
      (node (ref "R14") (pin "2") (pinfunction "2_2") (pintype "passive"))
      (node (ref "R15") (pin "2") (pinfunction "2_2") (pintype "passive"))
      (node (ref "R16") (pin "2") (pinfunction "2_2") (pintype "passive"))
      (node (ref "R22") (pin "2") (pinfunction "2_2") (pintype "passive"))
      (node (ref "R25") (pin "2") (pinfunction "2_2") (pintype "passive"))
      (node (ref "R26") (pin "2") (pinfunction "2_2") (pintype "passive"))
      (node (ref "R5") (pin "2") (pinfunction "2_2") (pintype "passive"))
      (node (ref "R6") (pin "2") (pinfunction "2_2") (pintype "passive"))
      (node (ref "R7") (pin "2") (pinfunction "2_2") (pintype "passive"))
      (node (ref "R8") (pin "2") (pinfunction "2_2") (pintype "passive"))
      (node (ref "R8*") (pin "2") (pinfunction "2_2") (pintype "passive"))
      (node (ref "R9") (pin "2") (pinfunction "2_2") (pintype "passive"))
      (node (ref "R9*") (pin "2") (pinfunction "2_2") (pintype "passive"))
      (node (ref "U1") (pin "16") (pinfunction "VCC_16") (pintype "power_in"))
      (node (ref "U2") (pin "2") (pinfunction "VDD_2") (pintype "passive"))
      (node (ref "U2") (pin "8") (pinfunction "A_8") (pintype "passive"))
      (node (ref "U3") (pin "7") (pinfunction "VOUT_7") (pintype "output"))
      (node (ref "X2") (pin "1") (pinfunction "SK_1") (pintype "passive"))
      (node (ref "X2") (pin "2") (pinfunction "SK_2") (pintype "passive"))
    )
    (net (code "119") (name "unconnected-(IC1-~{INT}-Pad13)") (class "Default")
      (node (ref "IC1") (pin "13") (pinfunction "~{INT}_13") (pintype "output"))
    )
    (net (code "120") (name "unconnected-(IC4-SQW{slash}OUT-Pad7)") (class "Default")
      (node (ref "IC4") (pin "7") (pinfunction "SQW/OUT_7") (pintype "output"))
    )
    (net (code "121") (name "unconnected-(J1-Pad2)") (class "Default")
      (node (ref "J1") (pin "2") (pinfunction "2_2") (pintype "passive"))
    )
    (net (code "122") (name "unconnected-(JP6-Pad9)") (class "Default")
      (node (ref "JP6") (pin "9") (pinfunction "9_9") (pintype "passive"))
    )
    (net (code "123") (name "unconnected-(JP6-Pad10)") (class "Default")
      (node (ref "JP6") (pin "10") (pinfunction "10_10") (pintype "passive"))
    )
    (net (code "124") (name "unconnected-(JP15-Pad1)") (class "Default")
      (node (ref "JP15") (pin "1") (pinfunction "1_1") (pintype "passive"))
    )
    (net (code "125") (name "unconnected-(JP15-Pad2)") (class "Default")
      (node (ref "JP15") (pin "2") (pinfunction "2_2") (pintype "passive"))
    )
    (net (code "126") (name "unconnected-(JP15-Pad3)") (class "Default")
      (node (ref "JP15") (pin "3") (pinfunction "3_3") (pintype "passive"))
    )
    (net (code "127") (name "unconnected-(JP15-Pad4)") (class "Default")
      (node (ref "JP15") (pin "4") (pinfunction "4_4") (pintype "passive"))
    )
    (net (code "128") (name "unconnected-(JP15-Pad5)") (class "Default")
      (node (ref "JP15") (pin "5") (pinfunction "5_5") (pintype "passive"))
    )
    (net (code "129") (name "unconnected-(JP15-Pad6)") (class "Default")
      (node (ref "JP15") (pin "6") (pinfunction "6_6") (pintype "passive"))
    )
    (net (code "130") (name "unconnected-(JP15-Pad7)") (class "Default")
      (node (ref "JP15") (pin "7") (pinfunction "7_7") (pintype "passive"))
    )
    (net (code "131") (name "unconnected-(JP15-Pad8)") (class "Default")
      (node (ref "JP15") (pin "8") (pinfunction "8_8") (pintype "passive"))
    )
    (net (code "132") (name "unconnected-(MISHA1-PadADC)") (class "Default")
      (node (ref "MISHA1") (pin "ADC") (pinfunction "ADC_ADC") (pintype "bidirectional"))
    )
    (net (code "133") (name "unconnected-(MISHA1-PadGPIO0)") (class "Default")
      (node (ref "MISHA1") (pin "GPIO0") (pinfunction "GPIO0_GPIO0") (pintype "bidirectional"))
    )
    (net (code "134") (name "unconnected-(MISHA1-PadGPIO2)") (class "Default")
      (node (ref "MISHA1") (pin "GPIO2") (pinfunction "GPIO2_GPIO2") (pintype "bidirectional"))
    )
    (net (code "135") (name "unconnected-(MISHA1-PadGPIO4)") (class "Default")
      (node (ref "MISHA1") (pin "GPIO4") (pinfunction "GPIO4_GPIO4") (pintype "bidirectional"))
    )
    (net (code "136") (name "unconnected-(MISHA1-PadGPIO5)") (class "Default")
      (node (ref "MISHA1") (pin "GPIO5") (pinfunction "GPIO5_GPIO5") (pintype "bidirectional"))
    )
    (net (code "137") (name "unconnected-(MISHA1-PadGPIO12)") (class "Default")
      (node (ref "MISHA1") (pin "GPIO12") (pinfunction "GPIO12_GPIO12") (pintype "bidirectional"))
    )
    (net (code "138") (name "unconnected-(MISHA1-PadGPIO13)") (class "Default")
      (node (ref "MISHA1") (pin "GPIO13") (pinfunction "GPIO13_GPIO13") (pintype "bidirectional"))
    )
    (net (code "139") (name "unconnected-(MISHA1-PadGPIO14)") (class "Default")
      (node (ref "MISHA1") (pin "GPIO14") (pinfunction "GPIO14_GPIO14") (pintype "bidirectional"))
    )
    (net (code "140") (name "unconnected-(MISHA1-PadGPIO16)") (class "Default")
      (node (ref "MISHA1") (pin "GPIO16") (pinfunction "GPIO16_GPIO16") (pintype "bidirectional"))
    )
    (net (code "141") (name "unconnected-(Q3A-D-Pad5)") (class "Default")
      (node (ref "Q3") (pin "5") (pinfunction "D_5") (pintype "passive"))
    )
    (net (code "142") (name "unconnected-(Q3B-D-Pad7)") (class "Default")
      (node (ref "Q3") (pin "7") (pinfunction "D_7") (pintype "passive"))
    )
    (net (code "143") (name "unconnected-(U2-B-Pad7)") (class "Default")
      (node (ref "U2") (pin "7") (pinfunction "B_7") (pintype "passive"))
    )
    (net (code "144") (name "unconnected-(U3-~{FAULT}-Pad6)") (class "Default")
      (node (ref "U3") (pin "6") (pinfunction "~{FAULT}_6") (pintype "output"))
    )
  )
)
